# air-quality-kit.net
KiCad netlist of a schematic drawn in EAGLE
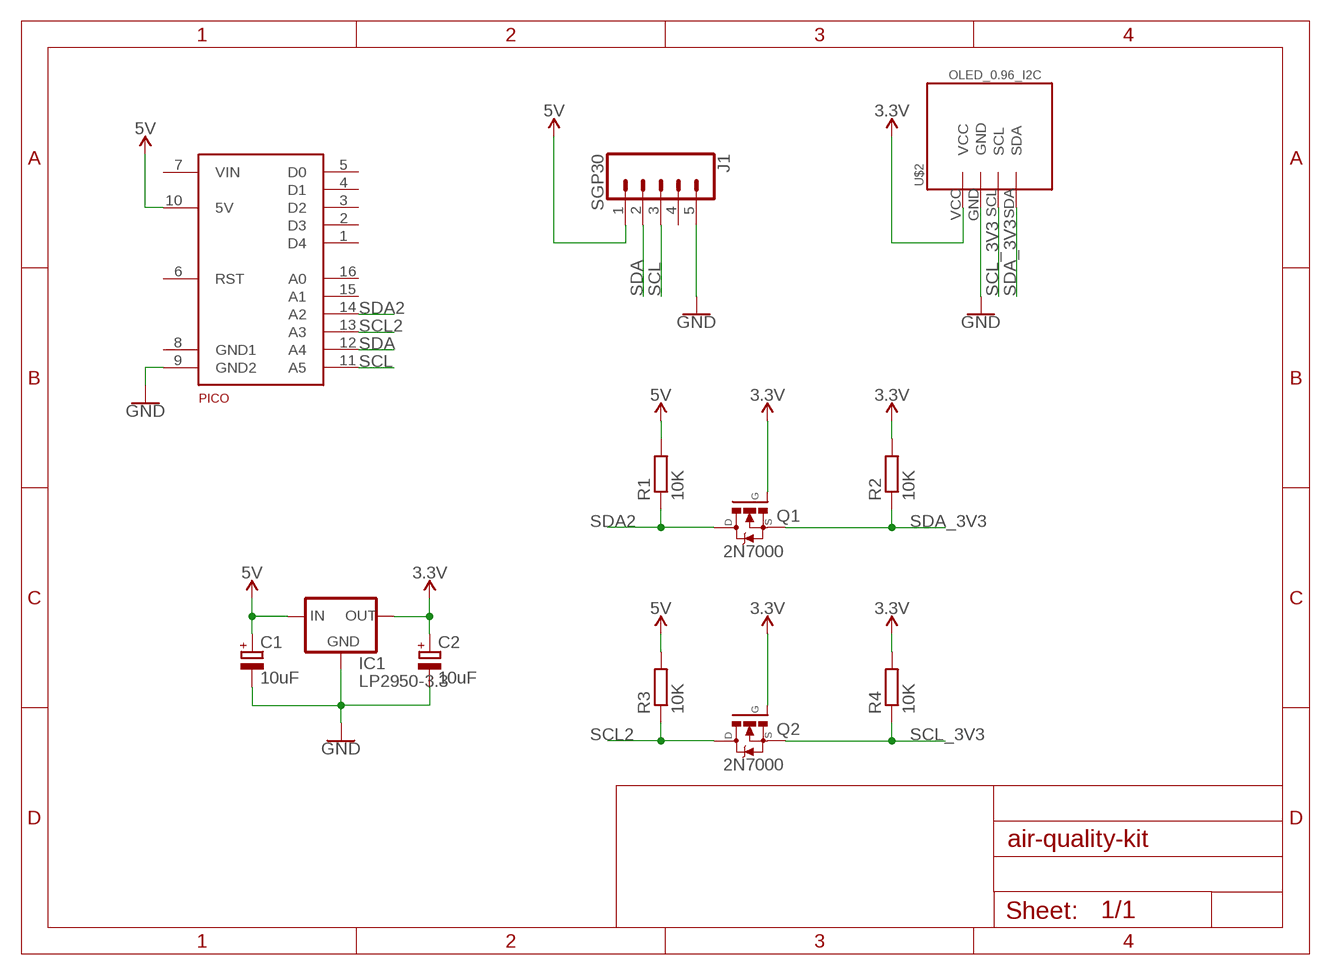
[diagram p0: schematic, sheet 1]

(export (version "E")
  (design (tool "Eeschema 10.0.6"))
  (components
    (comp (ref "C1")
      (value "10uF")
      (footprint "eagle-import:E2,5-5")
      (libsource (lib "eagle-import") (part "CPOL-EUE2.5-5"))
    )
    (comp (ref "C2")
      (value "10uF")
      (footprint "eagle-import:E2,5-5")
      (libsource (lib "eagle-import") (part "CPOL-EUE2.5-5"))
    )
    (comp (ref "IC1")
      (value "LP2950-3.3")
      (footprint "eagle-import:TO92")
      (libsource (lib "eagle-import") (part "LP2950?ACZ-3.3"))
    )
    (comp (ref "J1")
      (value "SGP30")
      (footprint "eagle-import:1X05")
      (libsource (lib "eagle-import") (part "CONN_05"))
    )
    (comp (ref "PICO")
      (value "PICO")
      (footprint "eagle-import:PICO")
      (libsource (lib "eagle-import") (part "PICO"))
    )
    (comp (ref "Q1")
      (value "2N7000")
      (footprint "eagle-import:TO-92")
      (fields (field (name "MF") "STMicroelectronics"))
      (libsource (lib "eagle-import") (part "2N7000"))
    )
    (comp (ref "Q2")
      (value "2N7000")
      (footprint "eagle-import:TO-92")
      (fields (field (name "MF") "STMicroelectronics"))
      (libsource (lib "eagle-import") (part "2N7000"))
    )
    (comp (ref "R1")
      (value "10K")
      (footprint "eagle-import:0207_10")
      (libsource (lib "eagle-import") (part "R-EU_0207/10"))
    )
    (comp (ref "R2")
      (value "10K")
      (footprint "eagle-import:0207_10")
      (libsource (lib "eagle-import") (part "R-EU_0207/10"))
    )
    (comp (ref "R3")
      (value "10K")
      (footprint "eagle-import:0207_10")
      (libsource (lib "eagle-import") (part "R-EU_0207/10"))
    )
    (comp (ref "R4")
      (value "10K")
      (footprint "eagle-import:0207_10")
      (libsource (lib "eagle-import") (part "R-EU_0207/10"))
    )
    (comp (ref "U$2")
      (value "OLED_0.96_I2C")
      (footprint "eagle-import:OLED_0.96_I2C")
      (libsource (lib "eagle-import") (part "OLED_0.96_I2C"))
    )
  )
  (nets
    (net (code "1") (name "/SCL") (class "Default")
      (node (ref "J1") (pin "3") (pinfunction "3_3") (pintype "passive"))
      (node (ref "PICO") (pin "11") (pinfunction "A5_11") (pintype "bidirectional"))
    )
    (net (code "2") (name "/SCL2") (class "Default")
      (node (ref "PICO") (pin "13") (pinfunction "A3_13") (pintype "bidirectional"))
      (node (ref "Q2") (pin "3") (pinfunction "D_3") (pintype "passive"))
      (node (ref "R3") (pin "1") (pinfunction "1_1") (pintype "passive"))
    )
    (net (code "3") (name "/SCL_3V3") (class "Default")
      (node (ref "Q2") (pin "1") (pinfunction "S_1") (pintype "passive"))
      (node (ref "R4") (pin "1") (pinfunction "1_1") (pintype "passive"))
      (node (ref "U$2") (pin "SCL") (pinfunction "SCL_SCL") (pintype "bidirectional"))
    )
    (net (code "4") (name "/SDA") (class "Default")
      (node (ref "J1") (pin "2") (pinfunction "2_2") (pintype "passive"))
      (node (ref "PICO") (pin "12") (pinfunction "A4_12") (pintype "bidirectional"))
    )
    (net (code "5") (name "/SDA2") (class "Default")
      (node (ref "PICO") (pin "14") (pinfunction "A2_14") (pintype "bidirectional"))
      (node (ref "Q1") (pin "3") (pinfunction "D_3") (pintype "passive"))
      (node (ref "R1") (pin "1") (pinfunction "1_1") (pintype "passive"))
    )
    (net (code "6") (name "/SDA_3V3") (class "Default")
      (node (ref "Q1") (pin "1") (pinfunction "S_1") (pintype "passive"))
      (node (ref "R2") (pin "1") (pinfunction "1_1") (pintype "passive"))
      (node (ref "U$2") (pin "SDA") (pinfunction "SDA_SDA") (pintype "bidirectional"))
    )
    (net (code "7") (name "3.3V") (class "Default")
      (node (ref "C2") (pin "+") (pinfunction "+_+") (pintype "passive"))
      (node (ref "IC1") (pin "1") (pinfunction "OUT_1") (pintype "passive"))
      (node (ref "Q1") (pin "2") (pinfunction "G_2") (pintype "passive"))
      (node (ref "Q2") (pin "2") (pinfunction "G_2") (pintype "passive"))
      (node (ref "R2") (pin "2") (pinfunction "2_2") (pintype "passive"))
      (node (ref "R4") (pin "2") (pinfunction "2_2") (pintype "passive"))
      (node (ref "U$2") (pin "VCC") (pinfunction "VCC_VCC") (pintype "bidirectional"))
    )
    (net (code "8") (name "5V") (class "Default")
      (node (ref "C1") (pin "+") (pinfunction "+_+") (pintype "passive"))
      (node (ref "IC1") (pin "3") (pinfunction "IN_3") (pintype "input"))
      (node (ref "J1") (pin "1") (pinfunction "1_1") (pintype "passive"))
      (node (ref "PICO") (pin "10") (pinfunction "5V_10") (pintype "bidirectional"))
      (node (ref "R1") (pin "2") (pinfunction "2_2") (pintype "passive"))
      (node (ref "R3") (pin "2") (pinfunction "2_2") (pintype "passive"))
    )
    (net (code "9") (name "GND") (class "Default")
      (node (ref "C1") (pin "-") (pinfunction "-_-") (pintype "passive"))
      (node (ref "C2") (pin "-") (pinfunction "-_-") (pintype "passive"))
      (node (ref "IC1") (pin "2") (pinfunction "GND_2") (pintype "input"))
      (node (ref "J1") (pin "5") (pinfunction "5_5") (pintype "passive"))
      (node (ref "PICO") (pin "9") (pinfunction "GND2_9") (pintype "bidirectional"))
      (node (ref "U$2") (pin "GND") (pinfunction "GND_GND") (pintype "bidirectional"))
    )
    (net (code "10") (name "unconnected-(J1-Pad4)") (class "Default")
      (node (ref "J1") (pin "4") (pinfunction "4_4") (pintype "passive"))
    )
    (net (code "11") (name "unconnected-(PICO-A0-Pad16)") (class "Default")
      (node (ref "PICO") (pin "16") (pinfunction "A0_16") (pintype "bidirectional"))
    )
    (net (code "12") (name "unconnected-(PICO-A1-Pad15)") (class "Default")
      (node (ref "PICO") (pin "15") (pinfunction "A1_15") (pintype "bidirectional"))
    )
    (net (code "13") (name "unconnected-(PICO-D0-Pad5)") (class "Default")
      (node (ref "PICO") (pin "5") (pinfunction "D0_5") (pintype "bidirectional"))
    )
    (net (code "14") (name "unconnected-(PICO-D1-Pad4)") (class "Default")
      (node (ref "PICO") (pin "4") (pinfunction "D1_4") (pintype "bidirectional"))
    )
    (net (code "15") (name "unconnected-(PICO-D2-Pad3)") (class "Default")
      (node (ref "PICO") (pin "3") (pinfunction "D2_3") (pintype "bidirectional"))
    )
    (net (code "16") (name "unconnected-(PICO-D3-Pad2)") (class "Default")
      (node (ref "PICO") (pin "2") (pinfunction "D3_2") (pintype "bidirectional"))
    )
    (net (code "17") (name "unconnected-(PICO-D4-Pad1)") (class "Default")
      (node (ref "PICO") (pin "1") (pinfunction "D4_1") (pintype "bidirectional"))
    )
    (net (code "18") (name "unconnected-(PICO-GND1-Pad8)") (class "Default")
      (node (ref "PICO") (pin "8") (pinfunction "GND1_8") (pintype "bidirectional"))
    )
    (net (code "19") (name "unconnected-(PICO-RST-Pad6)") (class "Default")
      (node (ref "PICO") (pin "6") (pinfunction "RST_6") (pintype "bidirectional"))
    )
    (net (code "20") (name "unconnected-(PICO-VIN-Pad7)") (class "Default")
      (node (ref "PICO") (pin "7") (pinfunction "VIN_7") (pintype "bidirectional"))
    )
  )
)
